# USBtoRS485.net
KiCad netlist of a schematic drawn in Altium Designer
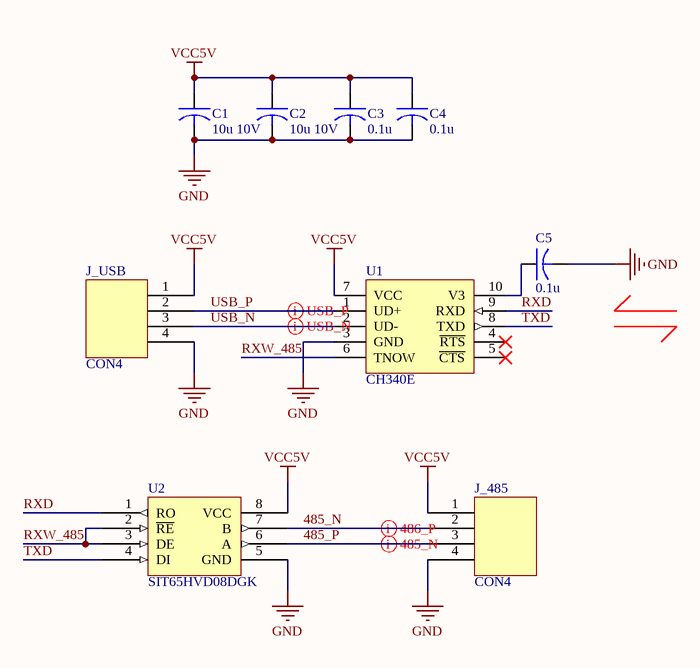
[diagram p0: USBtoRS485.SchDoc]

(export (version "E")
  (design (tool "Eeschema 10.0.6"))
  (components
    (comp (ref "C1")
      (value "10u 10V")
      (footprint "C0603")
      (description "C0603")
      (libsource (lib "USBtoRS485") (part "cap 0603"))
    )
    (comp (ref "C2")
      (value "10u 10V")
      (footprint "C0603")
      (description "C0603")
      (libsource (lib "USBtoRS485") (part "cap 0603"))
    )
    (comp (ref "C3")
      (value "0.1u")
      (footprint "C0402")
      (description "C0402")
      (libsource (lib "USBtoRS485") (part "cap 0402"))
    )
    (comp (ref "C4")
      (value "0.1u")
      (footprint "C0402")
      (description "C0402")
      (libsource (lib "USBtoRS485") (part "cap 0402"))
    )
    (comp (ref "C5")
      (value "0.1u")
      (footprint "C0402")
      (description "C0402")
      (libsource (lib "USBtoRS485") (part "cap 0402"))
    )
    (comp (ref "J_485") (value "CON4") (footprint "PH4") (libsource (lib "") (part "CON_4_1")))
    (comp (ref "J_USB") (value "CON4") (footprint "PH4") (libsource (lib "USBtoRS485") (part "CON_4")))
    (comp (ref "U1") (value "CH340E") (footprint "MSOP10") (libsource (lib "USBtoRS485") (part "CH340E")))
    (comp (ref "U2")
      (value "SIT65HVD08DGK")
      (footprint "MSOP8")
      (description "10Mbps RS422, RS485 Transceiver MSOP-8 RS-485/RS-422 ICs ROHS")
      (libsource (lib "USBtoRS485") (part "SIT65HVD08DGK"))
    )
  )
  (nets
    (net (code "1") (name "/485_N") (class "Default")
      (node (ref "J_485") (pin "2") (pinfunction "2_2") (pintype "passive"))
      (node (ref "U2") (pin "7") (pinfunction "B_7") (pintype "output"))
    )
    (net (code "2") (name "/485_P") (class "Default")
      (node (ref "J_485") (pin "3") (pinfunction "3_3") (pintype "passive"))
      (node (ref "U2") (pin "6") (pinfunction "A_6") (pintype "output"))
    )
    (net (code "3") (name "/RXD") (class "Default")
      (node (ref "U1") (pin "9") (pinfunction "RXD_9") (pintype "input"))
      (node (ref "U2") (pin "1") (pinfunction "RO_1") (pintype "output"))
    )
    (net (code "4") (name "/RXW_485") (class "Default")
      (node (ref "U1") (pin "6") (pinfunction "TNOW_6") (pintype "passive"))
      (node (ref "U2") (pin "2") (pinfunction "~{RE}_2") (pintype "input"))
      (node (ref "U2") (pin "3") (pinfunction "DE_3") (pintype "input"))
    )
    (net (code "5") (name "/TXD") (class "Default")
      (node (ref "U1") (pin "8") (pinfunction "TXD_8") (pintype "output"))
      (node (ref "U2") (pin "4") (pinfunction "DI_4") (pintype "input"))
    )
    (net (code "6") (name "/USB_N") (class "Default")
      (node (ref "J_USB") (pin "3") (pinfunction "3_3") (pintype "passive"))
      (node (ref "U1") (pin "2") (pinfunction "UD-_2") (pintype "passive"))
    )
    (net (code "7") (name "/USB_P") (class "Default")
      (node (ref "J_USB") (pin "2") (pinfunction "2_2") (pintype "passive"))
      (node (ref "U1") (pin "1") (pinfunction "UD+_1") (pintype "passive"))
    )
    (net (code "8") (name "GND") (class "Default")
      (node (ref "C1") (pin "2") (pinfunction "2_2") (pintype "passive"))
      (node (ref "C2") (pin "2") (pinfunction "2_2") (pintype "passive"))
      (node (ref "C3") (pin "2") (pinfunction "2_2") (pintype "passive"))
      (node (ref "C4") (pin "2") (pinfunction "2_2") (pintype "passive"))
      (node (ref "C5") (pin "2") (pinfunction "2_2") (pintype "passive"))
      (node (ref "J_485") (pin "4") (pinfunction "4_4") (pintype "passive"))
      (node (ref "J_USB") (pin "4") (pinfunction "4_4") (pintype "passive"))
      (node (ref "U1") (pin "3") (pinfunction "GND_3") (pintype "passive"))
      (node (ref "U2") (pin "5") (pinfunction "GND_5") (pintype "power_in"))
    )
    (net (code "9") (name "Net-(U1-V3)") (class "Default")
      (node (ref "C5") (pin "1") (pinfunction "1_1") (pintype "passive"))
      (node (ref "U1") (pin "10") (pinfunction "V3_10") (pintype "passive"))
    )
    (net (code "10") (name "VCC5V") (class "Default")
      (node (ref "C1") (pin "1") (pinfunction "1_1") (pintype "passive"))
      (node (ref "C2") (pin "1") (pinfunction "1_1") (pintype "passive"))
      (node (ref "C3") (pin "1") (pinfunction "1_1") (pintype "passive"))
      (node (ref "C4") (pin "1") (pinfunction "1_1") (pintype "passive"))
      (node (ref "J_485") (pin "1") (pinfunction "1_1") (pintype "passive"))
      (node (ref "J_USB") (pin "1") (pinfunction "1_1") (pintype "passive"))
      (node (ref "U1") (pin "7") (pinfunction "VCC_7") (pintype "passive"))
      (node (ref "U2") (pin "8") (pinfunction "VCC_8") (pintype "power_in"))
    )
    (net (code "11") (name "unconnected-(U1-~{CTS}-Pad5)") (class "Default")
      (node (ref "U1") (pin "5") (pinfunction "~{CTS}_5") (pintype "passive+no_connect"))
    )
    (net (code "12") (name "unconnected-(U1-~{RTS}-Pad4)") (class "Default")
      (node (ref "U1") (pin "4") (pinfunction "~{RTS}_4") (pintype "passive+no_connect"))
    )
  )
)
